# PCB_NEW_Tx.net
KiCad netlist of a schematic drawn in EAGLE
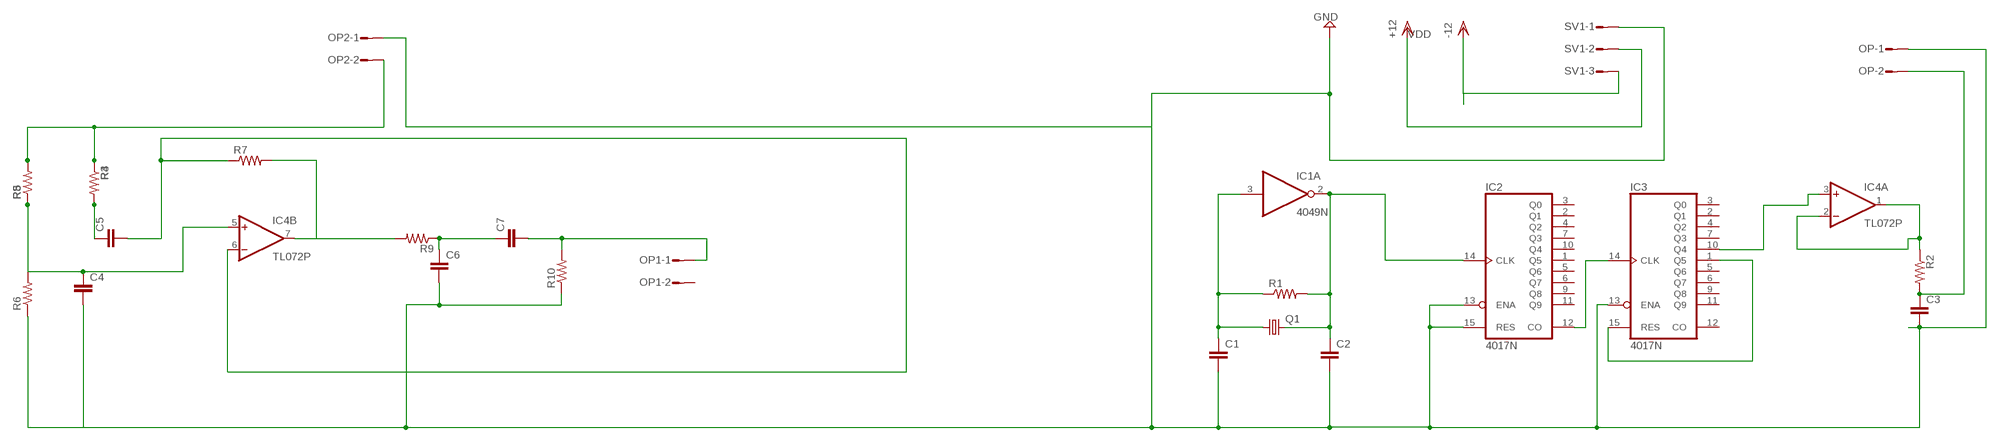
[diagram p0: schematic, sheet 1]

(export (version "E")
  (design (tool "Eeschema 10.0.6"))
  (components
    (comp (ref "C1")
      (value "C5/3.5")
      (footprint "eagle-import:C5B3.5")
      (libsource (lib "eagle-import") (part "C5/3.5"))
    )
    (comp (ref "C2")
      (value "C5/3.5")
      (footprint "eagle-import:C5B3.5")
      (libsource (lib "eagle-import") (part "C5/3.5"))
    )
    (comp (ref "C3")
      (value "C5/3.5")
      (footprint "eagle-import:C5B3.5")
      (libsource (lib "eagle-import") (part "C5/3.5"))
    )
    (comp (ref "C4")
      (value "C5/3.5")
      (footprint "eagle-import:C5B3.5")
      (libsource (lib "eagle-import") (part "C5/3.5"))
    )
    (comp (ref "C5")
      (value "C5/3.5")
      (footprint "eagle-import:C5B3.5")
      (libsource (lib "eagle-import") (part "C5/3.5"))
    )
    (comp (ref "C6")
      (value "C5/3.5")
      (footprint "eagle-import:C5B3.5")
      (libsource (lib "eagle-import") (part "C5/3.5"))
    )
    (comp (ref "C7")
      (value "C5/3.5")
      (footprint "eagle-import:C5B3.5")
      (libsource (lib "eagle-import") (part "C5/3.5"))
    )
    (comp (ref "IC1")
      (value "4049N")
      (footprint "eagle-import:DIL16")
      (libsource (lib "eagle-import") (part "4049N"))
    )
    (comp (ref "IC2")
      (value "4017N")
      (footprint "eagle-import:DIL16")
      (libsource (lib "eagle-import") (part "4017N"))
    )
    (comp (ref "IC3")
      (value "4017N")
      (footprint "eagle-import:DIL16")
      (libsource (lib "eagle-import") (part "4017N"))
    )
    (comp (ref "IC4")
      (value "TL072P")
      (footprint "eagle-import:DIL08")
      (libsource (lib "eagle-import") (part "TL072P"))
    )
    (comp (ref "OP")
      (value "L02P")
      (footprint "eagle-import:L02P")
      (libsource (lib "eagle-import") (part "L02P"))
    )
    (comp (ref "OP1")
      (value "L02P")
      (footprint "eagle-import:L02P")
      (libsource (lib "eagle-import") (part "L02P"))
    )
    (comp (ref "OP2")
      (value "L02P")
      (footprint "eagle-import:L02P")
      (libsource (lib "eagle-import") (part "L02P"))
    )
    (comp (ref "Q1")
      (value "CRYSTALHC33U-V")
      (footprint "eagle-import:HC33U-V")
      (libsource (lib "eagle-import") (part "CRYSTALHC33U-V"))
    )
    (comp (ref "R1")
      (value "R-US_0207/12")
      (footprint "eagle-import:0207_12")
      (libsource (lib "eagle-import") (part "R-US_0207/12"))
    )
    (comp (ref "R2")
      (value "R-US_0207/12")
      (footprint "eagle-import:0207_12")
      (libsource (lib "eagle-import") (part "R-US_0207/12"))
    )
    (comp (ref "R3")
      (value "R-US_0204/7")
      (footprint "eagle-import:0204_7")
      (libsource (lib "eagle-import") (part "R-US_0204/7"))
    )
    (comp (ref "R4")
      (value "R-US_0204/7")
      (footprint "eagle-import:0204_7")
      (libsource (lib "eagle-import") (part "R-US_0204/7"))
    )
    (comp (ref "R5")
      (value "R-US_0204/7")
      (footprint "eagle-import:0204_7")
      (libsource (lib "eagle-import") (part "R-US_0204/7"))
    )
    (comp (ref "R6")
      (value "R-US_0204/7")
      (footprint "eagle-import:0204_7")
      (libsource (lib "eagle-import") (part "R-US_0204/7"))
    )
    (comp (ref "R7")
      (value "R-US_0204/7")
      (footprint "eagle-import:0204_7")
      (libsource (lib "eagle-import") (part "R-US_0204/7"))
    )
    (comp (ref "R8")
      (value "R-US_0204/7")
      (footprint "eagle-import:0204_7")
      (libsource (lib "eagle-import") (part "R-US_0204/7"))
    )
    (comp (ref "R9")
      (value "R-US_0204/7")
      (footprint "eagle-import:0204_7")
      (libsource (lib "eagle-import") (part "R-US_0204/7"))
    )
    (comp (ref "R10")
      (value "R-US_0204/7")
      (footprint "eagle-import:0204_7")
      (libsource (lib "eagle-import") (part "R-US_0204/7"))
    )
    (comp (ref "SV1")
      (value "L03P")
      (footprint "eagle-import:L03P")
      (libsource (lib "eagle-import") (part "L03P"))
    )
  )
  (nets
    (net (code "1") (name "+12") (class "Default")
      (node (ref "SV1") (pin "2") (pinfunction "S_2") (pintype "passive"))
      (node (ref "SV1") (pin "3") (pinfunction "S_3") (pintype "passive"))
    )
    (net (code "2") (name "GND") (class "Default")
      (node (ref "C1") (pin "2") (pinfunction "2_2") (pintype "passive"))
      (node (ref "C2") (pin "2") (pinfunction "2_2") (pintype "passive"))
      (node (ref "C3") (pin "2") (pinfunction "2_2") (pintype "passive"))
      (node (ref "C4") (pin "2") (pinfunction "2_2") (pintype "passive"))
      (node (ref "C6") (pin "2") (pinfunction "2_2") (pintype "passive"))
      (node (ref "IC2") (pin "13") (pinfunction "ENA_13") (pintype "input"))
      (node (ref "IC2") (pin "15") (pinfunction "RES_15") (pintype "input"))
      (node (ref "IC3") (pin "13") (pinfunction "ENA_13") (pintype "input"))
      (node (ref "OP") (pin "1") (pinfunction "S_1") (pintype "passive"))
      (node (ref "OP2") (pin "1") (pinfunction "S_1") (pintype "passive"))
      (node (ref "R10") (pin "1") (pinfunction "1_1") (pintype "passive"))
      (node (ref "R6") (pin "1") (pinfunction "1_1") (pintype "passive"))
      (node (ref "SV1") (pin "1") (pinfunction "S_1") (pintype "passive"))
    )
    (net (code "3") (name "Net-(C5-Pad1)") (class "Default")
      (node (ref "C5") (pin "1") (pinfunction "1_1") (pintype "passive"))
      (node (ref "R3") (pin "2") (pinfunction "2_2") (pintype "passive"))
      (node (ref "R4") (pin "2") (pinfunction "2_2") (pintype "passive"))
    )
    (net (code "4") (name "Net-(C6-Pad1)") (class "Default")
      (node (ref "C6") (pin "1") (pinfunction "1_1") (pintype "passive"))
      (node (ref "C7") (pin "1") (pinfunction "1_1") (pintype "passive"))
      (node (ref "R9") (pin "1") (pinfunction "1_1") (pintype "passive"))
    )
    (net (code "5") (name "Net-(IC1A-I)") (class "Default")
      (node (ref "C1") (pin "1") (pinfunction "1_1") (pintype "passive"))
      (node (ref "IC1") (pin "3") (pinfunction "I_3") (pintype "input"))
      (node (ref "Q1") (pin "1") (pinfunction "1_1") (pintype "passive"))
      (node (ref "R1") (pin "1") (pinfunction "1_1") (pintype "passive"))
    )
    (net (code "6") (name "Net-(IC1A-O)") (class "Default")
      (node (ref "C2") (pin "1") (pinfunction "1_1") (pintype "passive"))
      (node (ref "IC1") (pin "2") (pinfunction "O_2") (pintype "output"))
      (node (ref "IC2") (pin "14") (pinfunction "CLK_14") (pintype "input"))
      (node (ref "Q1") (pin "2") (pinfunction "2_2") (pintype "passive"))
      (node (ref "R1") (pin "2") (pinfunction "2_2") (pintype "passive"))
    )
    (net (code "7") (name "Net-(IC2A-CO)") (class "Default")
      (node (ref "IC2") (pin "12") (pinfunction "CO_12") (pintype "output"))
      (node (ref "IC3") (pin "14") (pinfunction "CLK_14") (pintype "input"))
    )
    (net (code "8") (name "Net-(IC3A-Q4)") (class "Default")
      (node (ref "IC3") (pin "10") (pinfunction "Q4_10") (pintype "output"))
      (node (ref "IC4") (pin "3") (pinfunction "+IN_3") (pintype "input"))
    )
    (net (code "9") (name "Net-(IC3A-Q5)") (class "Default")
      (node (ref "IC3") (pin "1") (pinfunction "Q5_1") (pintype "output"))
      (node (ref "IC3") (pin "15") (pinfunction "RES_15") (pintype "input"))
    )
    (net (code "10") (name "Net-(IC4A--IN)") (class "Default")
      (node (ref "IC4") (pin "1") (pinfunction "OUT_1") (pintype "output"))
      (node (ref "IC4") (pin "2") (pinfunction "-IN_2") (pintype "input"))
      (node (ref "R2") (pin "1") (pinfunction "1_1") (pintype "passive"))
    )
    (net (code "11") (name "Net-(IC4B-+IN)") (class "Default")
      (node (ref "C4") (pin "1") (pinfunction "1_1") (pintype "passive"))
      (node (ref "IC4") (pin "5") (pinfunction "+IN_5") (pintype "input"))
      (node (ref "R5") (pin "1") (pinfunction "1_1") (pintype "passive"))
      (node (ref "R6") (pin "2") (pinfunction "2_2") (pintype "passive"))
      (node (ref "R8") (pin "1") (pinfunction "1_1") (pintype "passive"))
    )
    (net (code "12") (name "Net-(IC4B--IN)") (class "Default")
      (node (ref "C5") (pin "2") (pinfunction "2_2") (pintype "passive"))
      (node (ref "IC4") (pin "6") (pinfunction "-IN_6") (pintype "input"))
      (node (ref "R7") (pin "1") (pinfunction "1_1") (pintype "passive"))
    )
    (net (code "13") (name "Net-(IC4B-OUT)") (class "Default")
      (node (ref "IC4") (pin "7") (pinfunction "OUT_7") (pintype "output"))
      (node (ref "R7") (pin "2") (pinfunction "2_2") (pintype "passive"))
      (node (ref "R9") (pin "2") (pinfunction "2_2") (pintype "passive"))
    )
    (net (code "14") (name "Net-(OP1A-S)") (class "Default")
      (node (ref "C7") (pin "2") (pinfunction "2_2") (pintype "passive"))
      (node (ref "OP1") (pin "1") (pinfunction "S_1") (pintype "passive"))
      (node (ref "R10") (pin "2") (pinfunction "2_2") (pintype "passive"))
    )
    (net (code "15") (name "Net-(OP2B-S)") (class "Default")
      (node (ref "OP2") (pin "2") (pinfunction "S_2") (pintype "passive"))
      (node (ref "R3") (pin "1") (pinfunction "1_1") (pintype "passive"))
      (node (ref "R4") (pin "1") (pinfunction "1_1") (pintype "passive"))
      (node (ref "R5") (pin "2") (pinfunction "2_2") (pintype "passive"))
      (node (ref "R8") (pin "2") (pinfunction "2_2") (pintype "passive"))
    )
    (net (code "16") (name "Net-(OPB-S)") (class "Default")
      (node (ref "C3") (pin "1") (pinfunction "1_1") (pintype "passive"))
      (node (ref "OP") (pin "2") (pinfunction "S_2") (pintype "passive"))
      (node (ref "R2") (pin "2") (pinfunction "2_2") (pintype "passive"))
    )
    (net (code "17") (name "unconnected-(IC2A-Q0-Pad3)") (class "Default")
      (node (ref "IC2") (pin "3") (pinfunction "Q0_3") (pintype "output"))
    )
    (net (code "18") (name "unconnected-(IC2A-Q1-Pad2)") (class "Default")
      (node (ref "IC2") (pin "2") (pinfunction "Q1_2") (pintype "output"))
    )
    (net (code "19") (name "unconnected-(IC2A-Q2-Pad4)") (class "Default")
      (node (ref "IC2") (pin "4") (pinfunction "Q2_4") (pintype "output"))
    )
    (net (code "20") (name "unconnected-(IC2A-Q3-Pad7)") (class "Default")
      (node (ref "IC2") (pin "7") (pinfunction "Q3_7") (pintype "output"))
    )
    (net (code "21") (name "unconnected-(IC2A-Q4-Pad10)") (class "Default")
      (node (ref "IC2") (pin "10") (pinfunction "Q4_10") (pintype "output"))
    )
    (net (code "22") (name "unconnected-(IC2A-Q5-Pad1)") (class "Default")
      (node (ref "IC2") (pin "1") (pinfunction "Q5_1") (pintype "output"))
    )
    (net (code "23") (name "unconnected-(IC2A-Q6-Pad5)") (class "Default")
      (node (ref "IC2") (pin "5") (pinfunction "Q6_5") (pintype "output"))
    )
    (net (code "24") (name "unconnected-(IC2A-Q7-Pad6)") (class "Default")
      (node (ref "IC2") (pin "6") (pinfunction "Q7_6") (pintype "output"))
    )
    (net (code "25") (name "unconnected-(IC2A-Q8-Pad9)") (class "Default")
      (node (ref "IC2") (pin "9") (pinfunction "Q8_9") (pintype "output"))
    )
    (net (code "26") (name "unconnected-(IC2A-Q9-Pad11)") (class "Default")
      (node (ref "IC2") (pin "11") (pinfunction "Q9_11") (pintype "output"))
    )
    (net (code "27") (name "unconnected-(IC3A-CO-Pad12)") (class "Default")
      (node (ref "IC3") (pin "12") (pinfunction "CO_12") (pintype "output"))
    )
    (net (code "28") (name "unconnected-(IC3A-Q0-Pad3)") (class "Default")
      (node (ref "IC3") (pin "3") (pinfunction "Q0_3") (pintype "output"))
    )
    (net (code "29") (name "unconnected-(IC3A-Q1-Pad2)") (class "Default")
      (node (ref "IC3") (pin "2") (pinfunction "Q1_2") (pintype "output"))
    )
    (net (code "30") (name "unconnected-(IC3A-Q2-Pad4)") (class "Default")
      (node (ref "IC3") (pin "4") (pinfunction "Q2_4") (pintype "output"))
    )
    (net (code "31") (name "unconnected-(IC3A-Q3-Pad7)") (class "Default")
      (node (ref "IC3") (pin "7") (pinfunction "Q3_7") (pintype "output"))
    )
    (net (code "32") (name "unconnected-(IC3A-Q6-Pad5)") (class "Default")
      (node (ref "IC3") (pin "5") (pinfunction "Q6_5") (pintype "output"))
    )
    (net (code "33") (name "unconnected-(IC3A-Q7-Pad6)") (class "Default")
      (node (ref "IC3") (pin "6") (pinfunction "Q7_6") (pintype "output"))
    )
    (net (code "34") (name "unconnected-(IC3A-Q8-Pad9)") (class "Default")
      (node (ref "IC3") (pin "9") (pinfunction "Q8_9") (pintype "output"))
    )
    (net (code "35") (name "unconnected-(IC3A-Q9-Pad11)") (class "Default")
      (node (ref "IC3") (pin "11") (pinfunction "Q9_11") (pintype "output"))
    )
    (net (code "36") (name "unconnected-(OP1B-S-Pad2)") (class "Default")
      (node (ref "OP1") (pin "2") (pinfunction "S_2") (pintype "passive"))
    )
  )
)
